# Solenoise.net
KiCad netlist of a schematic drawn in EAGLE
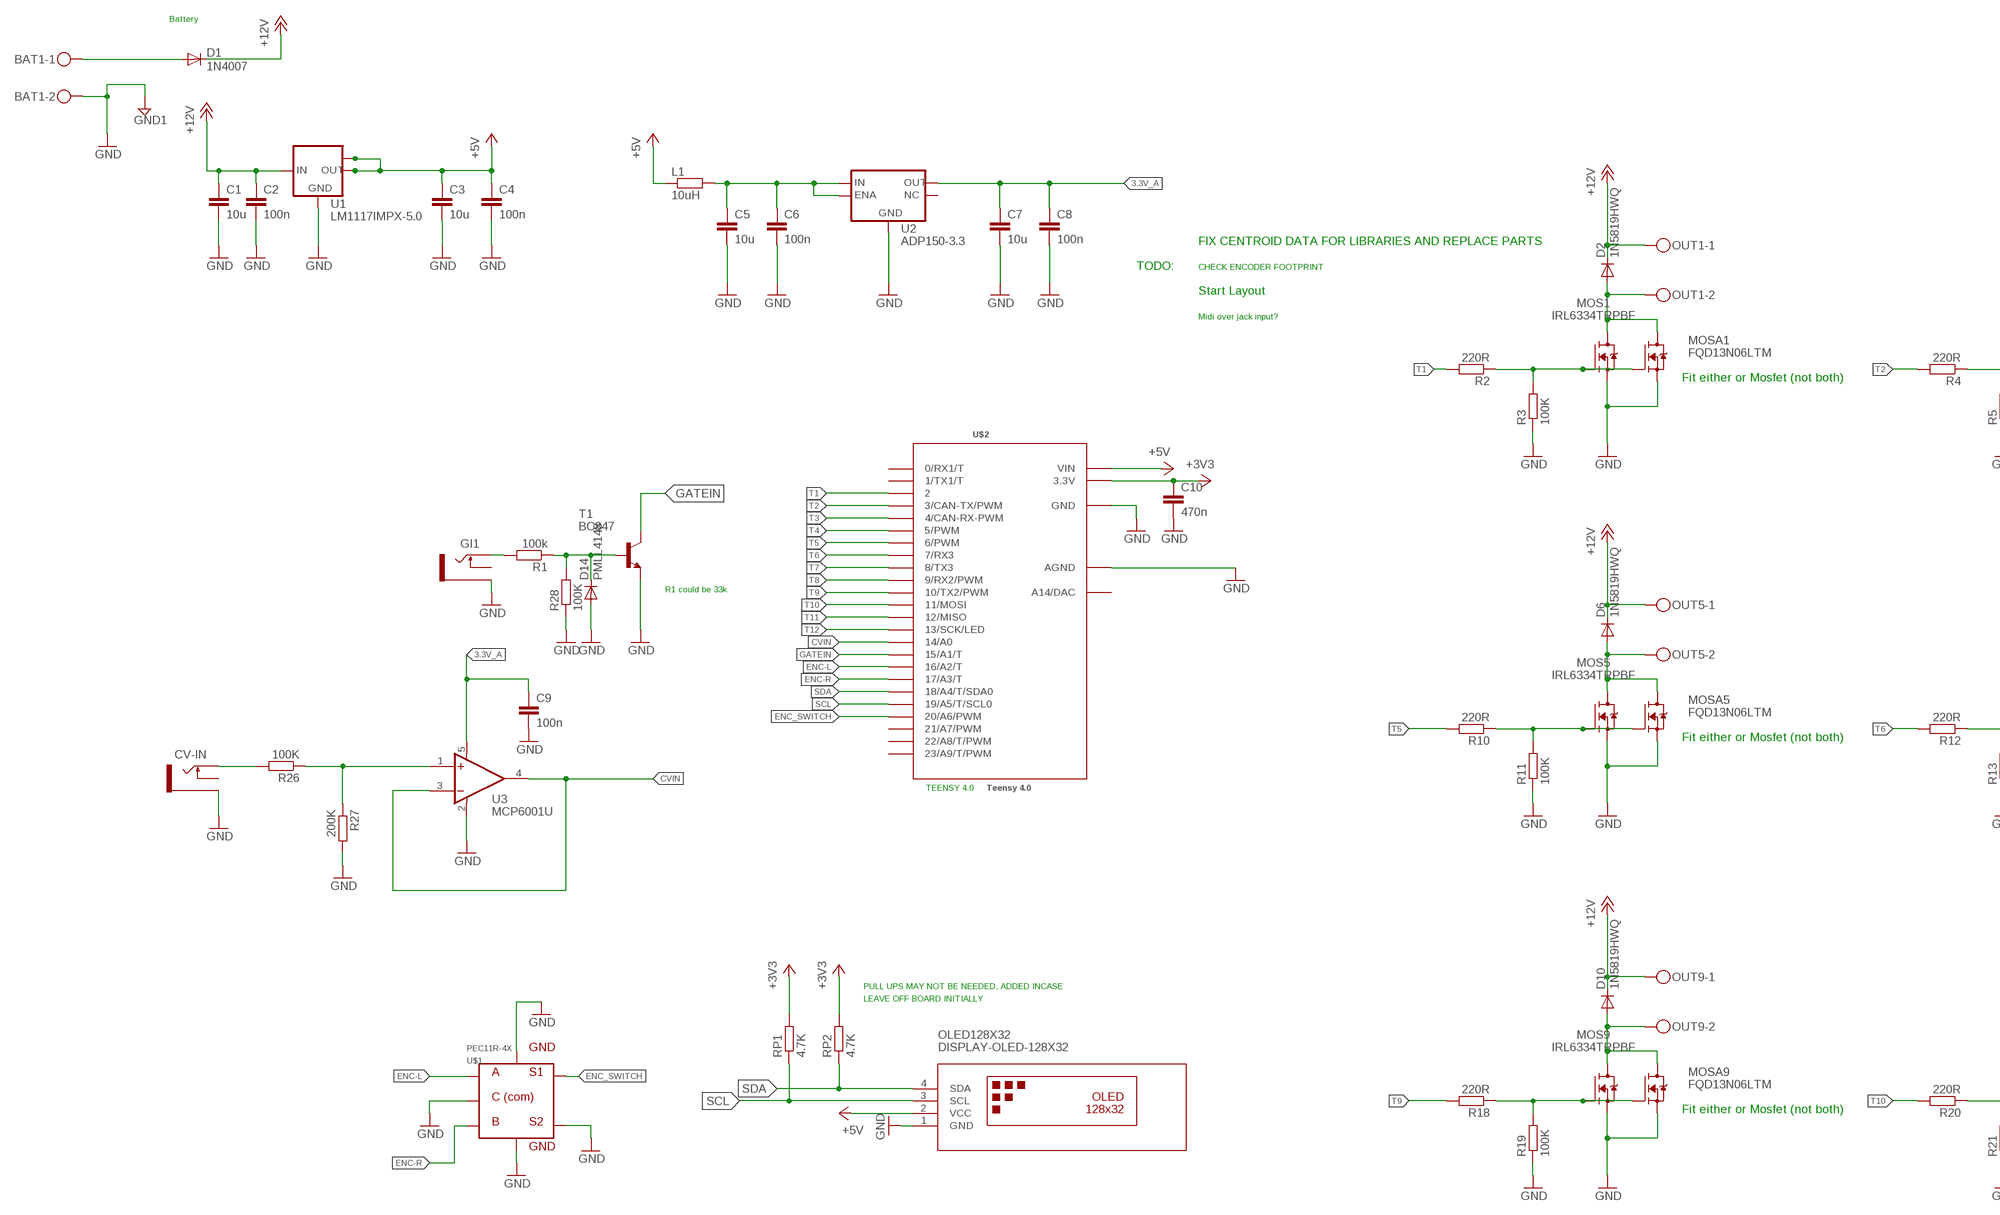
[diagram p0: schematic, sheet 1, part 1 of 2]
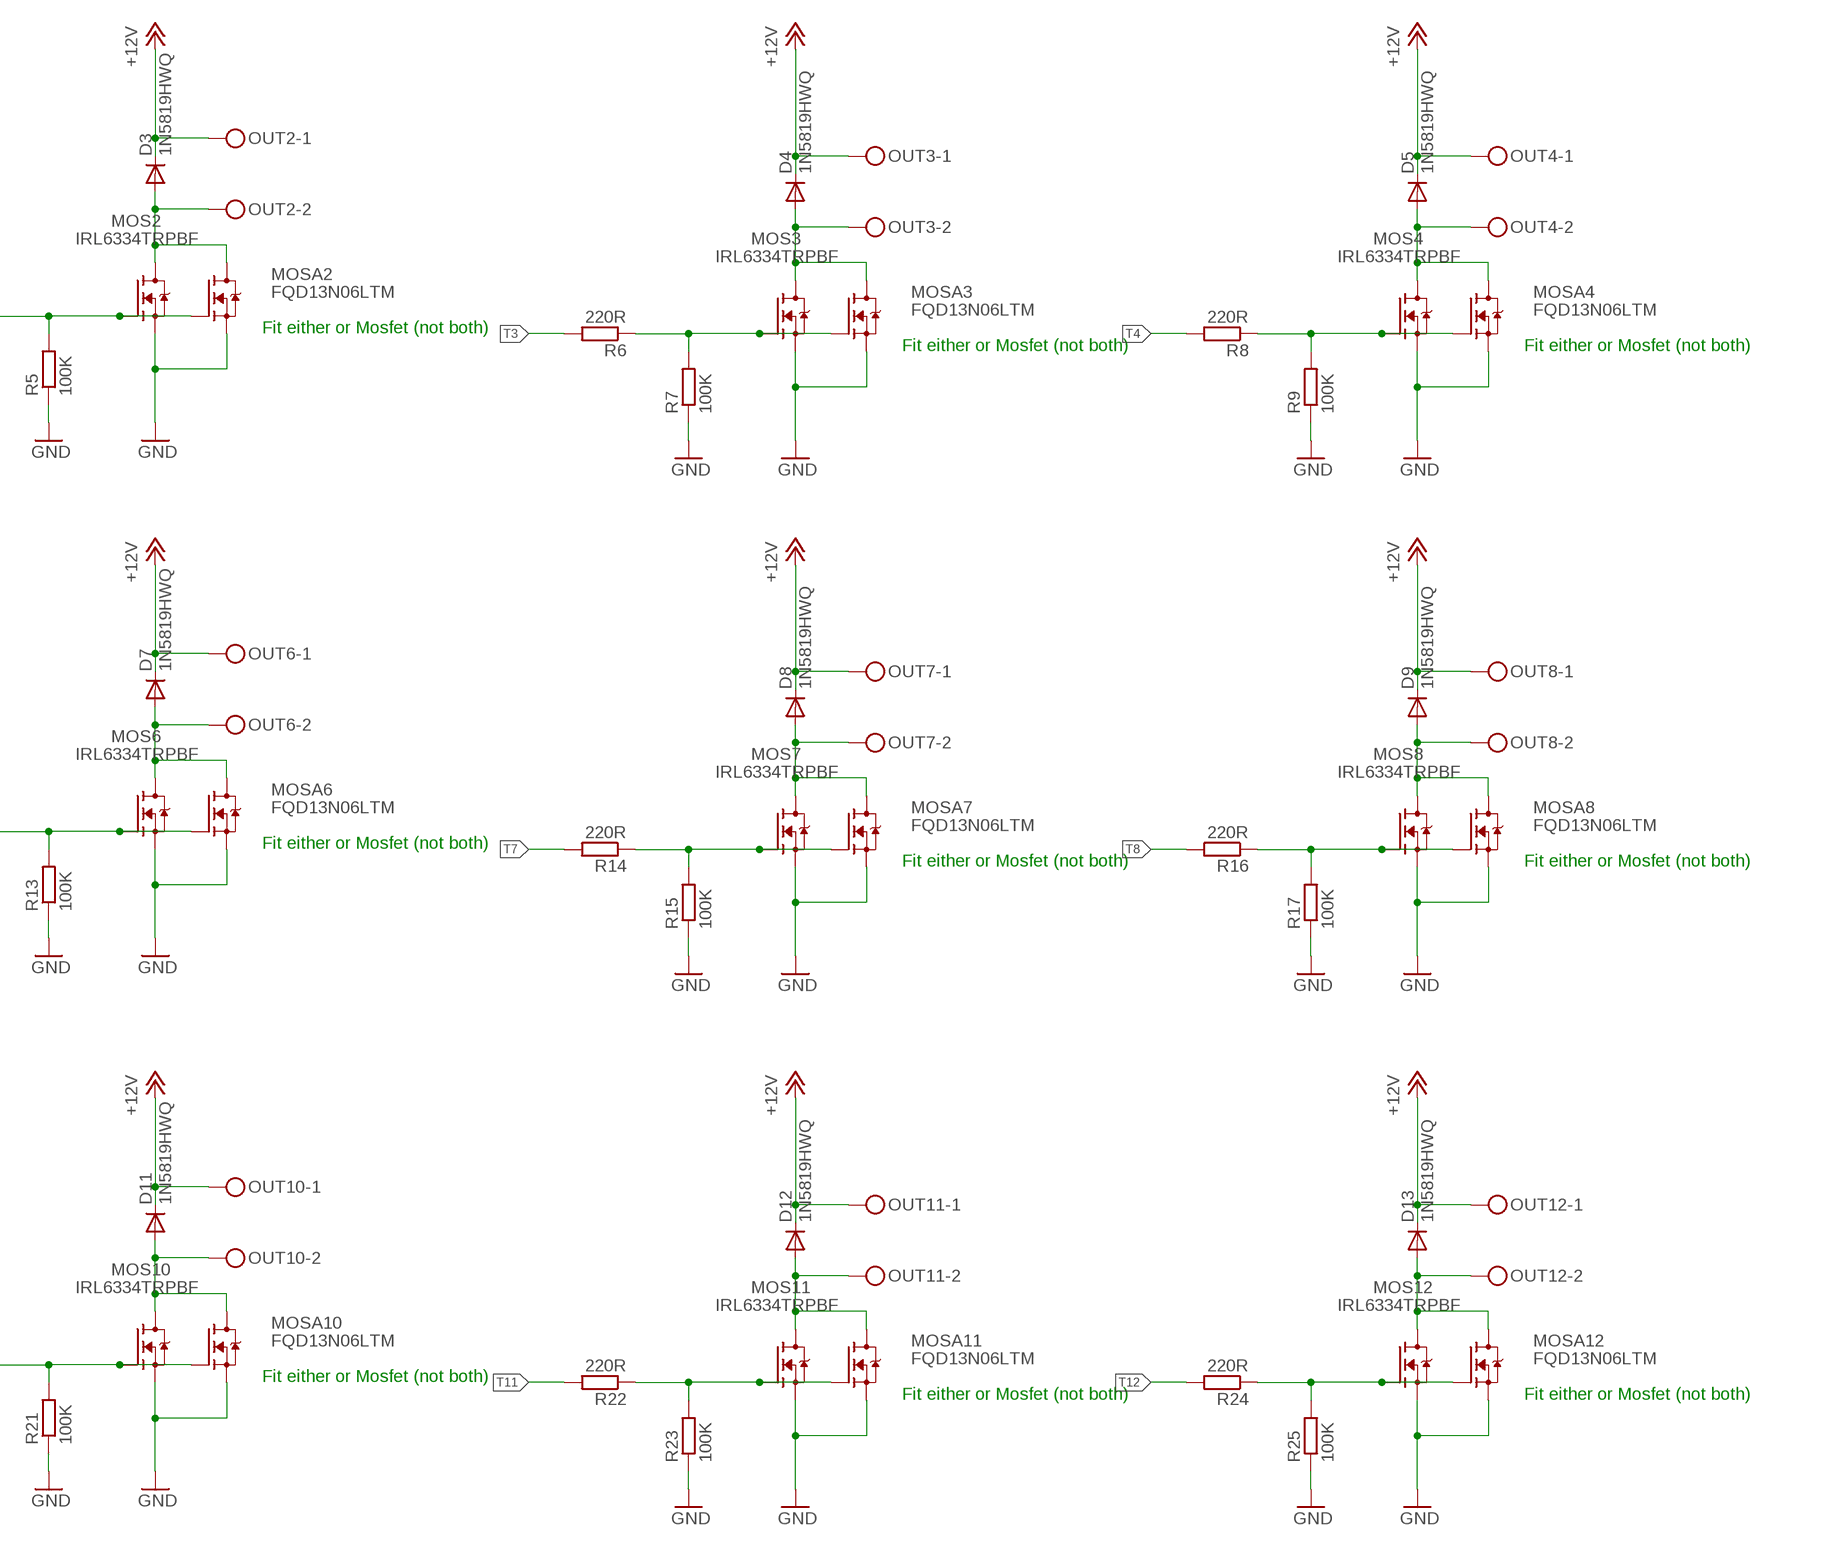
[diagram p1: schematic, sheet 1, part 2 of 2]

(export (version "E")
  (design (tool "Eeschema 10.0.6"))
  (components
    (comp (ref "BAT1")
      (value "MKDSN1,5/2-5,08")
      (footprint "eagle-import:MKDSN1,5_2-5,08")
      (fields (field (name "MPN") "MKDSN 1,5/2-5.08"))
      (libsource (lib "eagle-import") (part "MKDSN1,5/2-5,08"))
    )
    (comp (ref "C1")
      (value "10u")
      (footprint "eagle-import:C1206")
      (libsource (lib "eagle-import") (part "C-EUC1206"))
    )
    (comp (ref "C2")
      (value "100n")
      (footprint "eagle-import:C0805")
      (libsource (lib "eagle-import") (part "C-EUC0805"))
    )
    (comp (ref "C3")
      (value "10u")
      (footprint "eagle-import:C1206")
      (libsource (lib "eagle-import") (part "C-EUC1206"))
    )
    (comp (ref "C4")
      (value "100n")
      (footprint "eagle-import:C0805")
      (libsource (lib "eagle-import") (part "C-EUC0805"))
    )
    (comp (ref "C5")
      (value "10u")
      (footprint "eagle-import:C1206")
      (libsource (lib "eagle-import") (part "C-EUC1206"))
    )
    (comp (ref "C6")
      (value "100n")
      (footprint "eagle-import:C0805")
      (libsource (lib "eagle-import") (part "C-EUC0805"))
    )
    (comp (ref "C7")
      (value "10u")
      (footprint "eagle-import:C1206")
      (libsource (lib "eagle-import") (part "C-EUC1206"))
    )
    (comp (ref "C8")
      (value "100n")
      (footprint "eagle-import:C0805")
      (libsource (lib "eagle-import") (part "C-EUC0805"))
    )
    (comp (ref "C9")
      (value "100n")
      (footprint "eagle-import:C0805")
      (libsource (lib "eagle-import") (part "C-EUC0805"))
    )
    (comp (ref "C10")
      (value "470n")
      (footprint "eagle-import:C0805")
      (libsource (lib "eagle-import") (part "C-EUC0805"))
    )
    (comp (ref "CV-IN")
      (value "THONKICONNNEW")
      (footprint "eagle-import:WQP-PJ301M-12_JACK")
      (libsource (lib "eagle-import") (part "THONKICONNNEW"))
    )
    (comp (ref "D1")
      (value "1N4007")
      (footprint "eagle-import:DO41-10")
      (libsource (lib "eagle-import") (part "1N4004"))
    )
    (comp (ref "D2")
      (value "1N5819HWQ")
      (footprint "eagle-import:SOD123")
      (libsource (lib "eagle-import") (part "MBR0520LT"))
    )
    (comp (ref "D3")
      (value "1N5819HWQ")
      (footprint "eagle-import:SOD123")
      (libsource (lib "eagle-import") (part "MBR0520LT"))
    )
    (comp (ref "D4")
      (value "1N5819HWQ")
      (footprint "eagle-import:SOD123")
      (libsource (lib "eagle-import") (part "MBR0520LT"))
    )
    (comp (ref "D5")
      (value "1N5819HWQ")
      (footprint "eagle-import:SOD123")
      (libsource (lib "eagle-import") (part "MBR0520LT"))
    )
    (comp (ref "D6")
      (value "1N5819HWQ")
      (footprint "eagle-import:SOD123")
      (libsource (lib "eagle-import") (part "MBR0520LT"))
    )
    (comp (ref "D7")
      (value "1N5819HWQ")
      (footprint "eagle-import:SOD123")
      (libsource (lib "eagle-import") (part "MBR0520LT"))
    )
    (comp (ref "D8")
      (value "1N5819HWQ")
      (footprint "eagle-import:SOD123")
      (libsource (lib "eagle-import") (part "MBR0520LT"))
    )
    (comp (ref "D9")
      (value "1N5819HWQ")
      (footprint "eagle-import:SOD123")
      (libsource (lib "eagle-import") (part "MBR0520LT"))
    )
    (comp (ref "D10")
      (value "1N5819HWQ")
      (footprint "eagle-import:SOD123")
      (libsource (lib "eagle-import") (part "MBR0520LT"))
    )
    (comp (ref "D11")
      (value "1N5819HWQ")
      (footprint "eagle-import:SOD123")
      (libsource (lib "eagle-import") (part "MBR0520LT"))
    )
    (comp (ref "D12")
      (value "1N5819HWQ")
      (footprint "eagle-import:SOD123")
      (libsource (lib "eagle-import") (part "MBR0520LT"))
    )
    (comp (ref "D13")
      (value "1N5819HWQ")
      (footprint "eagle-import:SOD123")
      (libsource (lib "eagle-import") (part "MBR0520LT"))
    )
    (comp (ref "D14")
      (value "PMLL4148")
      (footprint "eagle-import:SOD80C")
      (libsource (lib "eagle-import") (part "PMLL4150"))
    )
    (comp (ref "GI1")
      (value "THONKICONNNEW")
      (footprint "eagle-import:WQP-PJ301M-12_JACK")
      (libsource (lib "eagle-import") (part "THONKICONNNEW"))
    )
    (comp (ref "L1")
      (value "10uH")
      (footprint "eagle-import:R0805")
      (libsource (lib "eagle-import") (part "R-EU_R0805"))
    )
    (comp (ref "MOS1")
      (value "IRL6334TRPBF")
      (footprint "eagle-import:IRL6344TRPBF")
      (libsource (lib "eagle-import") (part "IRL6334TRPBF"))
    )
    (comp (ref "MOS2")
      (value "IRL6334TRPBF")
      (footprint "eagle-import:IRL6344TRPBF")
      (libsource (lib "eagle-import") (part "IRL6334TRPBF"))
    )
    (comp (ref "MOS3")
      (value "IRL6334TRPBF")
      (footprint "eagle-import:IRL6344TRPBF")
      (libsource (lib "eagle-import") (part "IRL6334TRPBF"))
    )
    (comp (ref "MOS4")
      (value "IRL6334TRPBF")
      (footprint "eagle-import:IRL6344TRPBF")
      (libsource (lib "eagle-import") (part "IRL6334TRPBF"))
    )
    (comp (ref "MOS5")
      (value "IRL6334TRPBF")
      (footprint "eagle-import:IRL6344TRPBF")
      (libsource (lib "eagle-import") (part "IRL6334TRPBF"))
    )
    (comp (ref "MOS6")
      (value "IRL6334TRPBF")
      (footprint "eagle-import:IRL6344TRPBF")
      (libsource (lib "eagle-import") (part "IRL6334TRPBF"))
    )
    (comp (ref "MOS7")
      (value "IRL6334TRPBF")
      (footprint "eagle-import:IRL6344TRPBF")
      (libsource (lib "eagle-import") (part "IRL6334TRPBF"))
    )
    (comp (ref "MOS8")
      (value "IRL6334TRPBF")
      (footprint "eagle-import:IRL6344TRPBF")
      (libsource (lib "eagle-import") (part "IRL6334TRPBF"))
    )
    (comp (ref "MOS9")
      (value "IRL6334TRPBF")
      (footprint "eagle-import:IRL6344TRPBF")
      (libsource (lib "eagle-import") (part "IRL6334TRPBF"))
    )
    (comp (ref "MOS10")
      (value "IRL6334TRPBF")
      (footprint "eagle-import:IRL6344TRPBF")
      (libsource (lib "eagle-import") (part "IRL6334TRPBF"))
    )
    (comp (ref "MOS11")
      (value "IRL6334TRPBF")
      (footprint "eagle-import:IRL6344TRPBF")
      (libsource (lib "eagle-import") (part "IRL6334TRPBF"))
    )
    (comp (ref "MOS12")
      (value "IRL6334TRPBF")
      (footprint "eagle-import:IRL6344TRPBF")
      (libsource (lib "eagle-import") (part "IRL6334TRPBF"))
    )
    (comp (ref "MOSA1")
      (value "FQD13N06LTM")
      (footprint "eagle-import:FQD13N06LTM")
      (libsource (lib "eagle-import") (part "FQD13N06LTM"))
    )
    (comp (ref "MOSA2")
      (value "FQD13N06LTM")
      (footprint "eagle-import:FQD13N06LTM")
      (libsource (lib "eagle-import") (part "FQD13N06LTM"))
    )
    (comp (ref "MOSA3")
      (value "FQD13N06LTM")
      (footprint "eagle-import:FQD13N06LTM")
      (libsource (lib "eagle-import") (part "FQD13N06LTM"))
    )
    (comp (ref "MOSA4")
      (value "FQD13N06LTM")
      (footprint "eagle-import:FQD13N06LTM")
      (libsource (lib "eagle-import") (part "FQD13N06LTM"))
    )
    (comp (ref "MOSA5")
      (value "FQD13N06LTM")
      (footprint "eagle-import:FQD13N06LTM")
      (libsource (lib "eagle-import") (part "FQD13N06LTM"))
    )
    (comp (ref "MOSA6")
      (value "FQD13N06LTM")
      (footprint "eagle-import:FQD13N06LTM")
      (libsource (lib "eagle-import") (part "FQD13N06LTM"))
    )
    (comp (ref "MOSA7")
      (value "FQD13N06LTM")
      (footprint "eagle-import:FQD13N06LTM")
      (libsource (lib "eagle-import") (part "FQD13N06LTM"))
    )
    (comp (ref "MOSA8")
      (value "FQD13N06LTM")
      (footprint "eagle-import:FQD13N06LTM")
      (libsource (lib "eagle-import") (part "FQD13N06LTM"))
    )
    (comp (ref "MOSA9")
      (value "FQD13N06LTM")
      (footprint "eagle-import:FQD13N06LTM")
      (libsource (lib "eagle-import") (part "FQD13N06LTM"))
    )
    (comp (ref "MOSA10")
      (value "FQD13N06LTM")
      (footprint "eagle-import:FQD13N06LTM")
      (libsource (lib "eagle-import") (part "FQD13N06LTM"))
    )
    (comp (ref "MOSA11")
      (value "FQD13N06LTM")
      (footprint "eagle-import:FQD13N06LTM")
      (libsource (lib "eagle-import") (part "FQD13N06LTM"))
    )
    (comp (ref "MOSA12")
      (value "FQD13N06LTM")
      (footprint "eagle-import:FQD13N06LTM")
      (libsource (lib "eagle-import") (part "FQD13N06LTM"))
    )
    (comp (ref "OLED128X32")
      (value "DISPLAY-OLED-128X32")
      (footprint "eagle-import:DISPLAY-OLED-128X32")
      (libsource (lib "eagle-import") (part "DISPLAY-OLED-128X32"))
    )
    (comp (ref "OUT1")
      (value "MKDSN1,5/2-5,08")
      (footprint "eagle-import:MKDSN1,5_2-5,08")
      (fields (field (name "MPN") "MKDSN 1,5/2-5.08"))
      (libsource (lib "eagle-import") (part "MKDSN1,5/2-5,08"))
    )
    (comp (ref "OUT2")
      (value "MKDSN1,5/2-5,08")
      (footprint "eagle-import:MKDSN1,5_2-5,08")
      (fields (field (name "MPN") "MKDSN 1,5/2-5.08"))
      (libsource (lib "eagle-import") (part "MKDSN1,5/2-5,08"))
    )
    (comp (ref "OUT3")
      (value "MKDSN1,5/2-5,08")
      (footprint "eagle-import:MKDSN1,5_2-5,08")
      (fields (field (name "MPN") "MKDSN 1,5/2-5.08"))
      (libsource (lib "eagle-import") (part "MKDSN1,5/2-5,08"))
    )
    (comp (ref "OUT4")
      (value "MKDSN1,5/2-5,08")
      (footprint "eagle-import:MKDSN1,5_2-5,08")
      (fields (field (name "MPN") "MKDSN 1,5/2-5.08"))
      (libsource (lib "eagle-import") (part "MKDSN1,5/2-5,08"))
    )
    (comp (ref "OUT5")
      (value "MKDSN1,5/2-5,08")
      (footprint "eagle-import:MKDSN1,5_2-5,08")
      (fields (field (name "MPN") "MKDSN 1,5/2-5.08"))
      (libsource (lib "eagle-import") (part "MKDSN1,5/2-5,08"))
    )
    (comp (ref "OUT6")
      (value "MKDSN1,5/2-5,08")
      (footprint "eagle-import:MKDSN1,5_2-5,08")
      (fields (field (name "MPN") "MKDSN 1,5/2-5.08"))
      (libsource (lib "eagle-import") (part "MKDSN1,5/2-5,08"))
    )
    (comp (ref "OUT7")
      (value "MKDSN1,5/2-5,08")
      (footprint "eagle-import:MKDSN1,5_2-5,08")
      (fields (field (name "MPN") "MKDSN 1,5/2-5.08"))
      (libsource (lib "eagle-import") (part "MKDSN1,5/2-5,08"))
    )
    (comp (ref "OUT8")
      (value "MKDSN1,5/2-5,08")
      (footprint "eagle-import:MKDSN1,5_2-5,08")
      (fields (field (name "MPN") "MKDSN 1,5/2-5.08"))
      (libsource (lib "eagle-import") (part "MKDSN1,5/2-5,08"))
    )
    (comp (ref "OUT9")
      (value "MKDSN1,5/2-5,08")
      (footprint "eagle-import:MKDSN1,5_2-5,08")
      (fields (field (name "MPN") "MKDSN 1,5/2-5.08"))
      (libsource (lib "eagle-import") (part "MKDSN1,5/2-5,08"))
    )
    (comp (ref "OUT10")
      (value "MKDSN1,5/2-5,08")
      (footprint "eagle-import:MKDSN1,5_2-5,08")
      (fields (field (name "MPN") "MKDSN 1,5/2-5.08"))
      (libsource (lib "eagle-import") (part "MKDSN1,5/2-5,08"))
    )
    (comp (ref "OUT11")
      (value "MKDSN1,5/2-5,08")
      (footprint "eagle-import:MKDSN1,5_2-5,08")
      (fields (field (name "MPN") "MKDSN 1,5/2-5.08"))
      (libsource (lib "eagle-import") (part "MKDSN1,5/2-5,08"))
    )
    (comp (ref "OUT12")
      (value "MKDSN1,5/2-5,08")
      (footprint "eagle-import:MKDSN1,5_2-5,08")
      (fields (field (name "MPN") "MKDSN 1,5/2-5.08"))
      (libsource (lib "eagle-import") (part "MKDSN1,5/2-5,08"))
    )
    (comp (ref "R1")
      (value "100k")
      (footprint "eagle-import:R0805")
      (libsource (lib "eagle-import") (part "R-EU_R0805"))
    )
    (comp (ref "R2")
      (value "220R")
      (footprint "eagle-import:R0805")
      (libsource (lib "eagle-import") (part "R-EU_R0805"))
    )
    (comp (ref "R3")
      (value "100K")
      (footprint "eagle-import:R0805")
      (libsource (lib "eagle-import") (part "R-EU_R0805"))
    )
    (comp (ref "R4")
      (value "220R")
      (footprint "eagle-import:R0805")
      (libsource (lib "eagle-import") (part "R-EU_R0805"))
    )
    (comp (ref "R5")
      (value "100K")
      (footprint "eagle-import:R0805")
      (libsource (lib "eagle-import") (part "R-EU_R0805"))
    )
    (comp (ref "R6")
      (value "220R")
      (footprint "eagle-import:R0805")
      (libsource (lib "eagle-import") (part "R-EU_R0805"))
    )
    (comp (ref "R7")
      (value "100K")
      (footprint "eagle-import:R0805")
      (libsource (lib "eagle-import") (part "R-EU_R0805"))
    )
    (comp (ref "R8")
      (value "220R")
      (footprint "eagle-import:R0805")
      (libsource (lib "eagle-import") (part "R-EU_R0805"))
    )
    (comp (ref "R9")
      (value "100K")
      (footprint "eagle-import:R0805")
      (libsource (lib "eagle-import") (part "R-EU_R0805"))
    )
    (comp (ref "R10")
      (value "220R")
      (footprint "eagle-import:R0805")
      (libsource (lib "eagle-import") (part "R-EU_R0805"))
    )
    (comp (ref "R11")
      (value "100K")
      (footprint "eagle-import:R0805")
      (libsource (lib "eagle-import") (part "R-EU_R0805"))
    )
    (comp (ref "R12")
      (value "220R")
      (footprint "eagle-import:R0805")
      (libsource (lib "eagle-import") (part "R-EU_R0805"))
    )
    (comp (ref "R13")
      (value "100K")
      (footprint "eagle-import:R0805")
      (libsource (lib "eagle-import") (part "R-EU_R0805"))
    )
    (comp (ref "R14")
      (value "220R")
      (footprint "eagle-import:R0805")
      (libsource (lib "eagle-import") (part "R-EU_R0805"))
    )
    (comp (ref "R15")
      (value "100K")
      (footprint "eagle-import:R0805")
      (libsource (lib "eagle-import") (part "R-EU_R0805"))
    )
    (comp (ref "R16")
      (value "220R")
      (footprint "eagle-import:R0805")
      (libsource (lib "eagle-import") (part "R-EU_R0805"))
    )
    (comp (ref "R17")
      (value "100K")
      (footprint "eagle-import:R0805")
      (libsource (lib "eagle-import") (part "R-EU_R0805"))
    )
    (comp (ref "R18")
      (value "220R")
      (footprint "eagle-import:R0805")
      (libsource (lib "eagle-import") (part "R-EU_R0805"))
    )
    (comp (ref "R19")
      (value "100K")
      (footprint "eagle-import:R0805")
      (libsource (lib "eagle-import") (part "R-EU_R0805"))
    )
    (comp (ref "R20")
      (value "220R")
      (footprint "eagle-import:R0805")
      (libsource (lib "eagle-import") (part "R-EU_R0805"))
    )
    (comp (ref "R21")
      (value "100K")
      (footprint "eagle-import:R0805")
      (libsource (lib "eagle-import") (part "R-EU_R0805"))
    )
    (comp (ref "R22")
      (value "220R")
      (footprint "eagle-import:R0805")
      (libsource (lib "eagle-import") (part "R-EU_R0805"))
    )
    (comp (ref "R23")
      (value "100K")
      (footprint "eagle-import:R0805")
      (libsource (lib "eagle-import") (part "R-EU_R0805"))
    )
    (comp (ref "R24")
      (value "220R")
      (footprint "eagle-import:R0805")
      (libsource (lib "eagle-import") (part "R-EU_R0805"))
    )
    (comp (ref "R25")
      (value "100K")
      (footprint "eagle-import:R0805")
      (libsource (lib "eagle-import") (part "R-EU_R0805"))
    )
    (comp (ref "R26")
      (value "100K")
      (footprint "eagle-import:R0805")
      (libsource (lib "eagle-import") (part "R-EU_R0805"))
    )
    (comp (ref "R27")
      (value "200K")
      (footprint "eagle-import:R0805")
      (libsource (lib "eagle-import") (part "R-EU_R0805"))
    )
    (comp (ref "R28")
      (value "100K")
      (footprint "eagle-import:R0805")
      (libsource (lib "eagle-import") (part "R-EU_R0805"))
    )
    (comp (ref "RP1")
      (value "4.7K")
      (footprint "eagle-import:R0805")
      (libsource (lib "eagle-import") (part "R-EU_R0805"))
    )
    (comp (ref "RP2")
      (value "4.7K")
      (footprint "eagle-import:R0805")
      (libsource (lib "eagle-import") (part "R-EU_R0805"))
    )
    (comp (ref "T1")
      (value "BC847")
      (footprint "eagle-import:SOT23")
      (libsource (lib "eagle-import") (part "BC847"))
    )
    (comp (ref "U$1")
      (value "PEC11R-4X")
      (footprint "eagle-import:ENC")
      (libsource (lib "eagle-import") (part "PEC11R-4X"))
    )
    (comp (ref "U$2")
      (value "Teensy 4.0")
      (footprint "eagle-import:TEENSY_3.1_DAC")
      (libsource (lib "eagle-import") (part "TEENSY_3.1_DAC"))
    )
    (comp (ref "U1")
      (value "LM1117IMPX-5.0")
      (footprint "eagle-import:SOT223")
      (libsource (lib "eagle-import") (part "LM1117IMPX-5.0"))
    )
    (comp (ref "U2")
      (value "ADP150-3.3")
      (footprint "eagle-import:SOT23-5")
      (libsource (lib "eagle-import") (part "ADP150-3.3"))
    )
    (comp (ref "U3")
      (value "MCP6001U")
      (footprint "eagle-import:MCP6001")
      (libsource (lib "eagle-import") (part "MCP6001U"))
    )
  )
  (nets
    (net (code "1") (name "+3V3") (class "Default")
      (node (ref "C10") (pin "1") (pinfunction "1_1") (pintype "passive"))
      (node (ref "RP1") (pin "2") (pinfunction "2_2") (pintype "passive"))
      (node (ref "RP2") (pin "2") (pinfunction "2_2") (pintype "passive"))
      (node (ref "U$2") (pin "3.3V") (pinfunction "3.3V_3.3V") (pintype "power_in"))
    )
    (net (code "2") (name "+5V") (class "Default")
      (node (ref "C3") (pin "1") (pinfunction "1_1") (pintype "passive"))
      (node (ref "C4") (pin "1") (pinfunction "1_1") (pintype "passive"))
      (node (ref "L1") (pin "1") (pinfunction "1_1") (pintype "passive"))
      (node (ref "OLED128X32") (pin "2") (pinfunction "VCC_2") (pintype "power_in"))
      (node (ref "U$2") (pin "VIN") (pinfunction "VIN_VIN") (pintype "power_in"))
      (node (ref "U1") (pin "2") (pinfunction "OUT_2") (pintype "passive"))
      (node (ref "U1") (pin "TAB") (pinfunction "OUT1_TAB") (pintype "passive"))
    )
    (net (code "3") (name "+12V") (class "Default")
      (node (ref "C1") (pin "1") (pinfunction "1_1") (pintype "passive"))
      (node (ref "C2") (pin "1") (pinfunction "1_1") (pintype "passive"))
      (node (ref "D1") (pin "C") (pinfunction "C_C") (pintype "passive"))
      (node (ref "D10") (pin "C") (pinfunction "C_C") (pintype "passive"))
      (node (ref "D11") (pin "C") (pinfunction "C_C") (pintype "passive"))
      (node (ref "D12") (pin "C") (pinfunction "C_C") (pintype "passive"))
      (node (ref "D13") (pin "C") (pinfunction "C_C") (pintype "passive"))
      (node (ref "D2") (pin "C") (pinfunction "C_C") (pintype "passive"))
      (node (ref "D3") (pin "C") (pinfunction "C_C") (pintype "passive"))
      (node (ref "D4") (pin "C") (pinfunction "C_C") (pintype "passive"))
      (node (ref "D5") (pin "C") (pinfunction "C_C") (pintype "passive"))
      (node (ref "D6") (pin "C") (pinfunction "C_C") (pintype "passive"))
      (node (ref "D7") (pin "C") (pinfunction "C_C") (pintype "passive"))
      (node (ref "D8") (pin "C") (pinfunction "C_C") (pintype "passive"))
      (node (ref "D9") (pin "C") (pinfunction "C_C") (pintype "passive"))
      (node (ref "OUT1") (pin "1") (pinfunction "KL_1") (pintype "passive"))
      (node (ref "OUT10") (pin "1") (pinfunction "KL_1") (pintype "passive"))
      (node (ref "OUT11") (pin "1") (pinfunction "KL_1") (pintype "passive"))
      (node (ref "OUT12") (pin "1") (pinfunction "KL_1") (pintype "passive"))
      (node (ref "OUT2") (pin "1") (pinfunction "KL_1") (pintype "passive"))
      (node (ref "OUT3") (pin "1") (pinfunction "KL_1") (pintype "passive"))
      (node (ref "OUT4") (pin "1") (pinfunction "KL_1") (pintype "passive"))
      (node (ref "OUT5") (pin "1") (pinfunction "KL_1") (pintype "passive"))
      (node (ref "OUT6") (pin "1") (pinfunction "KL_1") (pintype "passive"))
      (node (ref "OUT7") (pin "1") (pinfunction "KL_1") (pintype "passive"))
      (node (ref "OUT8") (pin "1") (pinfunction "KL_1") (pintype "passive"))
      (node (ref "OUT9") (pin "1") (pinfunction "KL_1") (pintype "passive"))
      (node (ref "U1") (pin "3") (pinfunction "IN_3") (pintype "input"))
    )
    (net (code "4") (name "3.3V_A") (class "Default")
      (node (ref "C7") (pin "1") (pinfunction "1_1") (pintype "passive"))
      (node (ref "C8") (pin "1") (pinfunction "1_1") (pintype "passive"))
      (node (ref "C9") (pin "1") (pinfunction "1_1") (pintype "passive"))
      (node (ref "U2") (pin "OUT") (pinfunction "VOUT_OUT") (pintype "passive"))
      (node (ref "U3") (pin "5") (pinfunction "V+_5") (pintype "power_in"))
    )
    (net (code "5") (name "CVIN") (class "Default")
      (node (ref "U$2") (pin "14/A0") (pinfunction "14/A0_14/A0") (pintype "bidirectional"))
      (node (ref "U3") (pin "3") (pinfunction "-IN_3") (pintype "input"))
      (node (ref "U3") (pin "4") (pinfunction "OUT_4") (pintype "output"))
    )
    (net (code "6") (name "ENC-L") (class "Default")
      (node (ref "U$1") (pin "A") (pinfunction "A_A") (pintype "passive"))
      (node (ref "U$2") (pin "16/A2") (pinfunction "16/A2/T_16/A2") (pintype "bidirectional"))
    )
    (net (code "7") (name "ENC-R") (class "Default")
      (node (ref "U$1") (pin "B") (pinfunction "B_B") (pintype "passive"))
      (node (ref "U$2") (pin "17/A3") (pinfunction "17/A3/T_17/A3") (pintype "bidirectional"))
    )
    (net (code "8") (name "ENC_SWITCH") (class "Default")
      (node (ref "U$1") (pin "1") (pinfunction "SW1_1") (pintype "passive"))
      (node (ref "U$2") (pin "20/A6") (pinfunction "20/A6/PWM_20/A6") (pintype "bidirectional"))
    )
    (net (code "9") (name "GATEIN") (class "Default")
      (node (ref "T1") (pin "3") (pinfunction "C_3") (pintype "passive"))
      (node (ref "U$2") (pin "15/A1") (pinfunction "15/A1/T_15/A1") (pintype "bidirectional"))
    )
    (net (code "10") (name "GND") (class "Default")
      (node (ref "BAT1") (pin "2") (pinfunction "KL_2") (pintype "passive"))
      (node (ref "C1") (pin "2") (pinfunction "2_2") (pintype "passive"))
      (node (ref "C10") (pin "2") (pinfunction "2_2") (pintype "passive"))
      (node (ref "C2") (pin "2") (pinfunction "2_2") (pintype "passive"))
      (node (ref "C3") (pin "2") (pinfunction "2_2") (pintype "passive"))
      (node (ref "C4") (pin "2") (pinfunction "2_2") (pintype "passive"))
      (node (ref "C5") (pin "2") (pinfunction "2_2") (pintype "passive"))
      (node (ref "C6") (pin "2") (pinfunction "2_2") (pintype "passive"))
      (node (ref "C7") (pin "2") (pinfunction "2_2") (pintype "passive"))
      (node (ref "C8") (pin "2") (pinfunction "2_2") (pintype "passive"))
      (node (ref "C9") (pin "2") (pinfunction "2_2") (pintype "passive"))
      (node (ref "CV-IN") (pin "P$3_SLEEVE") (pinfunction "SLEEVE_P$3_SLEEVE") (pintype "passive"))
      (node (ref "D14") (pin "A") (pinfunction "A_A") (pintype "passive"))
      (node (ref "GI1") (pin "P$3_SLEEVE") (pinfunction "SLEEVE_P$3_SLEEVE") (pintype "passive"))
      (node (ref "MOS1") (pin "2") (pinfunction "S_2") (pintype "passive"))
      (node (ref "MOS10") (pin "2") (pinfunction "S_2") (pintype "passive"))
      (node (ref "MOS11") (pin "2") (pinfunction "S_2") (pintype "passive"))
      (node (ref "MOS12") (pin "2") (pinfunction "S_2") (pintype "passive"))
      (node (ref "MOS2") (pin "2") (pinfunction "S_2") (pintype "passive"))
      (node (ref "MOS3") (pin "2") (pinfunction "S_2") (pintype "passive"))
      (node (ref "MOS4") (pin "2") (pinfunction "S_2") (pintype "passive"))
      (node (ref "MOS5") (pin "2") (pinfunction "S_2") (pintype "passive"))
      (node (ref "MOS6") (pin "2") (pinfunction "S_2") (pintype "passive"))
      (node (ref "MOS7") (pin "2") (pinfunction "S_2") (pintype "passive"))
      (node (ref "MOS8") (pin "2") (pinfunction "S_2") (pintype "passive"))
      (node (ref "MOS9") (pin "2") (pinfunction "S_2") (pintype "passive"))
      (node (ref "MOSA1") (pin "2") (pinfunction "S_2") (pintype "passive"))
      (node (ref "MOSA10") (pin "2") (pinfunction "S_2") (pintype "passive"))
      (node (ref "MOSA11") (pin "2") (pinfunction "S_2") (pintype "passive"))
      (node (ref "MOSA12") (pin "2") (pinfunction "S_2") (pintype "passive"))
      (node (ref "MOSA2") (pin "2") (pinfunction "S_2") (pintype "passive"))
      (node (ref "MOSA3") (pin "2") (pinfunction "S_2") (pintype "passive"))
      (node (ref "MOSA4") (pin "2") (pinfunction "S_2") (pintype "passive"))
      (node (ref "MOSA5") (pin "2") (pinfunction "S_2") (pintype "passive"))
      (node (ref "MOSA6") (pin "2") (pinfunction "S_2") (pintype "passive"))
      (node (ref "MOSA7") (pin "2") (pinfunction "S_2") (pintype "passive"))
      (node (ref "MOSA8") (pin "2") (pinfunction "S_2") (pintype "passive"))
      (node (ref "MOSA9") (pin "2") (pinfunction "S_2") (pintype "passive"))
      (node (ref "OLED128X32") (pin "1") (pinfunction "GND_1") (pintype "power_in"))
      (node (ref "R11") (pin "1") (pinfunction "1_1") (pintype "passive"))
      (node (ref "R13") (pin "1") (pinfunction "1_1") (pintype "passive"))
      (node (ref "R15") (pin "1") (pinfunction "1_1") (pintype "passive"))
      (node (ref "R17") (pin "1") (pinfunction "1_1") (pintype "passive"))
      (node (ref "R19") (pin "1") (pinfunction "1_1") (pintype "passive"))
      (node (ref "R21") (pin "1") (pinfunction "1_1") (pintype "passive"))
      (node (ref "R23") (pin "1") (pinfunction "1_1") (pintype "passive"))
      (node (ref "R25") (pin "1") (pinfunction "1_1") (pintype "passive"))
      (node (ref "R27") (pin "2") (pinfunction "2_2") (pintype "passive"))
      (node (ref "R28") (pin "1") (pinfunction "1_1") (pintype "passive"))
      (node (ref "R3") (pin "1") (pinfunction "1_1") (pintype "passive"))
      (node (ref "R5") (pin "1") (pinfunction "1_1") (pintype "passive"))
      (node (ref "R7") (pin "1") (pinfunction "1_1") (pintype "passive"))
      (node (ref "R9") (pin "1") (pinfunction "1_1") (pintype "passive"))
      (node (ref "T1") (pin "2") (pinfunction "E_2") (pintype "passive"))
      (node (ref "U$1") (pin "2") (pinfunction "SW2_2") (pintype "passive"))
      (node (ref "U$1") (pin "C") (pinfunction "C_C") (pintype "passive"))
      (node (ref "U$1") (pin "GND1") (pinfunction "GND1_GND1") (pintype "passive"))
      (node (ref "U$1") (pin "GND2") (pinfunction "GND2_GND2") (pintype "passive"))
      (node (ref "U$2") (pin "AGND") (pinfunction "AGND_AGND") (pintype "power_in"))
      (node (ref "U$2") (pin "GND") (pinfunction "GND_GND") (pintype "power_in"))
      (node (ref "U1") (pin "1") (pinfunction "GND_1") (pintype "input"))
      (node (ref "U2") (pin "GND") (pinfunction "GND_GND") (pintype "input"))
      (node (ref "U3") (pin "2") (pinfunction "V-_2") (pintype "power_in"))
    )
    (net (code "11") (name "Net-(BAT1A-KL)") (class "Default")
      (node (ref "BAT1") (pin "1") (pinfunction "KL_1") (pintype "passive"))
      (node (ref "D1") (pin "A") (pinfunction "A_A") (pintype "passive"))
    )
    (net (code "12") (name "Net-(CV-IN-TIP)") (class "Default")
      (node (ref "CV-IN") (pin "P$1_TIP") (pinfunction "TIP_P$1_TIP") (pintype "passive"))
      (node (ref "R26") (pin "2") (pinfunction "2_2") (pintype "passive"))
    )
    (net (code "13") (name "Net-(GI1-TIP)") (class "Default")
      (node (ref "GI1") (pin "P$1_TIP") (pinfunction "TIP_P$1_TIP") (pintype "passive"))
      (node (ref "R1") (pin "2") (pinfunction "2_2") (pintype "passive"))
    )
    (net (code "14") (name "Net-(MOS1-D)") (class "Default")
      (node (ref "D2") (pin "A") (pinfunction "A_A") (pintype "passive"))
      (node (ref "MOS1") (pin "3") (pinfunction "D_3") (pintype "passive"))
      (node (ref "MOSA1") (pin "3") (pinfunction "D_3") (pintype "passive"))
      (node (ref "OUT1") (pin "2") (pinfunction "KL_2") (pintype "passive"))
    )
    (net (code "15") (name "Net-(MOS1-G)") (class "Default")
      (node (ref "MOS1") (pin "1") (pinfunction "G_1") (pintype "passive"))
      (node (ref "MOSA1") (pin "1") (pinfunction "G_1") (pintype "passive"))
      (node (ref "R2") (pin "1") (pinfunction "1_1") (pintype "passive"))
      (node (ref "R3") (pin "2") (pinfunction "2_2") (pintype "passive"))
    )
    (net (code "16") (name "Net-(MOS2-D)") (class "Default")
      (node (ref "D3") (pin "A") (pinfunction "A_A") (pintype "passive"))
      (node (ref "MOS2") (pin "3") (pinfunction "D_3") (pintype "passive"))
      (node (ref "MOSA2") (pin "3") (pinfunction "D_3") (pintype "passive"))
      (node (ref "OUT2") (pin "2") (pinfunction "KL_2") (pintype "passive"))
    )
    (net (code "17") (name "Net-(MOS2-G)") (class "Default")
      (node (ref "MOS2") (pin "1") (pinfunction "G_1") (pintype "passive"))
      (node (ref "MOSA2") (pin "1") (pinfunction "G_1") (pintype "passive"))
      (node (ref "R4") (pin "1") (pinfunction "1_1") (pintype "passive"))
      (node (ref "R5") (pin "2") (pinfunction "2_2") (pintype "passive"))
    )
    (net (code "18") (name "Net-(MOS3-D)") (class "Default")
      (node (ref "D4") (pin "A") (pinfunction "A_A") (pintype "passive"))
      (node (ref "MOS3") (pin "3") (pinfunction "D_3") (pintype "passive"))
      (node (ref "MOSA3") (pin "3") (pinfunction "D_3") (pintype "passive"))
      (node (ref "OUT3") (pin "2") (pinfunction "KL_2") (pintype "passive"))
    )
    (net (code "19") (name "Net-(MOS3-G)") (class "Default")
      (node (ref "MOS3") (pin "1") (pinfunction "G_1") (pintype "passive"))
      (node (ref "MOSA3") (pin "1") (pinfunction "G_1") (pintype "passive"))
      (node (ref "R6") (pin "1") (pinfunction "1_1") (pintype "passive"))
      (node (ref "R7") (pin "2") (pinfunction "2_2") (pintype "passive"))
    )
    (net (code "20") (name "Net-(MOS4-D)") (class "Default")
      (node (ref "D5") (pin "A") (pinfunction "A_A") (pintype "passive"))
      (node (ref "MOS4") (pin "3") (pinfunction "D_3") (pintype "passive"))
      (node (ref "MOSA4") (pin "3") (pinfunction "D_3") (pintype "passive"))
      (node (ref "OUT4") (pin "2") (pinfunction "KL_2") (pintype "passive"))
    )
    (net (code "21") (name "Net-(MOS4-G)") (class "Default")
      (node (ref "MOS4") (pin "1") (pinfunction "G_1") (pintype "passive"))
      (node (ref "MOSA4") (pin "1") (pinfunction "G_1") (pintype "passive"))
      (node (ref "R8") (pin "1") (pinfunction "1_1") (pintype "passive"))
      (node (ref "R9") (pin "2") (pinfunction "2_2") (pintype "passive"))
    )
    (net (code "22") (name "Net-(MOS5-D)") (class "Default")
      (node (ref "D6") (pin "A") (pinfunction "A_A") (pintype "passive"))
      (node (ref "MOS5") (pin "3") (pinfunction "D_3") (pintype "passive"))
      (node (ref "MOSA5") (pin "3") (pinfunction "D_3") (pintype "passive"))
      (node (ref "OUT5") (pin "2") (pinfunction "KL_2") (pintype "passive"))
    )
    (net (code "23") (name "Net-(MOS5-G)") (class "Default")
      (node (ref "MOS5") (pin "1") (pinfunction "G_1") (pintype "passive"))
      (node (ref "MOSA5") (pin "1") (pinfunction "G_1") (pintype "passive"))
      (node (ref "R10") (pin "1") (pinfunction "1_1") (pintype "passive"))
      (node (ref "R11") (pin "2") (pinfunction "2_2") (pintype "passive"))
    )
    (net (code "24") (name "Net-(MOS6-D)") (class "Default")
      (node (ref "D7") (pin "A") (pinfunction "A_A") (pintype "passive"))
      (node (ref "MOS6") (pin "3") (pinfunction "D_3") (pintype "passive"))
      (node (ref "MOSA6") (pin "3") (pinfunction "D_3") (pintype "passive"))
      (node (ref "OUT6") (pin "2") (pinfunction "KL_2") (pintype "passive"))
    )
    (net (code "25") (name "Net-(MOS6-G)") (class "Default")
      (node (ref "MOS6") (pin "1") (pinfunction "G_1") (pintype "passive"))
      (node (ref "MOSA6") (pin "1") (pinfunction "G_1") (pintype "passive"))
      (node (ref "R12") (pin "1") (pinfunction "1_1") (pintype "passive"))
      (node (ref "R13") (pin "2") (pinfunction "2_2") (pintype "passive"))
    )
    (net (code "26") (name "Net-(MOS7-D)") (class "Default")
      (node (ref "D8") (pin "A") (pinfunction "A_A") (pintype "passive"))
      (node (ref "MOS7") (pin "3") (pinfunction "D_3") (pintype "passive"))
      (node (ref "MOSA7") (pin "3") (pinfunction "D_3") (pintype "passive"))
      (node (ref "OUT7") (pin "2") (pinfunction "KL_2") (pintype "passive"))
    )
    (net (code "27") (name "Net-(MOS7-G)") (class "Default")
      (node (ref "MOS7") (pin "1") (pinfunction "G_1") (pintype "passive"))
      (node (ref "MOSA7") (pin "1") (pinfunction "G_1") (pintype "passive"))
      (node (ref "R14") (pin "1") (pinfunction "1_1") (pintype "passive"))
      (node (ref "R15") (pin "2") (pinfunction "2_2") (pintype "passive"))
    )
    (net (code "28") (name "Net-(MOS8-D)") (class "Default")
      (node (ref "D9") (pin "A") (pinfunction "A_A") (pintype "passive"))
      (node (ref "MOS8") (pin "3") (pinfunction "D_3") (pintype "passive"))
      (node (ref "MOSA8") (pin "3") (pinfunction "D_3") (pintype "passive"))
      (node (ref "OUT8") (pin "2") (pinfunction "KL_2") (pintype "passive"))
    )
    (net (code "29") (name "Net-(MOS8-G)") (class "Default")
      (node (ref "MOS8") (pin "1") (pinfunction "G_1") (pintype "passive"))
      (node (ref "MOSA8") (pin "1") (pinfunction "G_1") (pintype "passive"))
      (node (ref "R16") (pin "1") (pinfunction "1_1") (pintype "passive"))
      (node (ref "R17") (pin "2") (pinfunction "2_2") (pintype "passive"))
    )
    (net (code "30") (name "Net-(MOS9-D)") (class "Default")
      (node (ref "D10") (pin "A") (pinfunction "A_A") (pintype "passive"))
      (node (ref "MOS9") (pin "3") (pinfunction "D_3") (pintype "passive"))
      (node (ref "MOSA9") (pin "3") (pinfunction "D_3") (pintype "passive"))
      (node (ref "OUT9") (pin "2") (pinfunction "KL_2") (pintype "passive"))
    )
    (net (code "31") (name "Net-(MOS9-G)") (class "Default")
      (node (ref "MOS9") (pin "1") (pinfunction "G_1") (pintype "passive"))
      (node (ref "MOSA9") (pin "1") (pinfunction "G_1") (pintype "passive"))
      (node (ref "R18") (pin "1") (pinfunction "1_1") (pintype "passive"))
      (node (ref "R19") (pin "2") (pinfunction "2_2") (pintype "passive"))
    )
    (net (code "32") (name "Net-(MOS10-D)") (class "Default")
      (node (ref "D11") (pin "A") (pinfunction "A_A") (pintype "passive"))
      (node (ref "MOS10") (pin "3") (pinfunction "D_3") (pintype "passive"))
      (node (ref "MOSA10") (pin "3") (pinfunction "D_3") (pintype "passive"))
      (node (ref "OUT10") (pin "2") (pinfunction "KL_2") (pintype "passive"))
    )
    (net (code "33") (name "Net-(MOS10-G)") (class "Default")
      (node (ref "MOS10") (pin "1") (pinfunction "G_1") (pintype "passive"))
      (node (ref "MOSA10") (pin "1") (pinfunction "G_1") (pintype "passive"))
      (node (ref "R20") (pin "1") (pinfunction "1_1") (pintype "passive"))
      (node (ref "R21") (pin "2") (pinfunction "2_2") (pintype "passive"))
    )
    (net (code "34") (name "Net-(MOS11-D)") (class "Default")
      (node (ref "D12") (pin "A") (pinfunction "A_A") (pintype "passive"))
      (node (ref "MOS11") (pin "3") (pinfunction "D_3") (pintype "passive"))
      (node (ref "MOSA11") (pin "3") (pinfunction "D_3") (pintype "passive"))
      (node (ref "OUT11") (pin "2") (pinfunction "KL_2") (pintype "passive"))
    )
    (net (code "35") (name "Net-(MOS11-G)") (class "Default")
      (node (ref "MOS11") (pin "1") (pinfunction "G_1") (pintype "passive"))
      (node (ref "MOSA11") (pin "1") (pinfunction "G_1") (pintype "passive"))
      (node (ref "R22") (pin "1") (pinfunction "1_1") (pintype "passive"))
      (node (ref "R23") (pin "2") (pinfunction "2_2") (pintype "passive"))
    )
    (net (code "36") (name "Net-(MOS12-D)") (class "Default")
      (node (ref "D13") (pin "A") (pinfunction "A_A") (pintype "passive"))
      (node (ref "MOS12") (pin "3") (pinfunction "D_3") (pintype "passive"))
      (node (ref "MOSA12") (pin "3") (pinfunction "D_3") (pintype "passive"))
      (node (ref "OUT12") (pin "2") (pinfunction "KL_2") (pintype "passive"))
    )
    (net (code "37") (name "Net-(MOS12-G)") (class "Default")
      (node (ref "MOS12") (pin "1") (pinfunction "G_1") (pintype "passive"))
      (node (ref "MOSA12") (pin "1") (pinfunction "G_1") (pintype "passive"))
      (node (ref "R24") (pin "1") (pinfunction "1_1") (pintype "passive"))
      (node (ref "R25") (pin "2") (pinfunction "2_2") (pintype "passive"))
    )
    (net (code "38") (name "Net-(T1-B)") (class "Default")
      (node (ref "D14") (pin "C") (pinfunction "C_C") (pintype "passive"))
      (node (ref "R1") (pin "1") (pinfunction "1_1") (pintype "passive"))
      (node (ref "R28") (pin "2") (pinfunction "2_2") (pintype "passive"))
      (node (ref "T1") (pin "1") (pinfunction "B_1") (pintype "passive"))
    )
    (net (code "39") (name "Net-(U2-ENA)") (class "Default")
      (node (ref "C5") (pin "1") (pinfunction "1_1") (pintype "passive"))
      (node (ref "C6") (pin "1") (pinfunction "1_1") (pintype "passive"))
      (node (ref "L1") (pin "2") (pinfunction "2_2") (pintype "passive"))
      (node (ref "U2") (pin "EN") (pinfunction "ENA_EN") (pintype "input"))
      (node (ref "U2") (pin "VIN") (pinfunction "IN_VIN") (pintype "input"))
    )
    (net (code "40") (name "Net-(U3-+IN)") (class "Default")
      (node (ref "R26") (pin "1") (pinfunction "1_1") (pintype "passive"))
      (node (ref "R27") (pin "1") (pinfunction "1_1") (pintype "passive"))
      (node (ref "U3") (pin "1") (pinfunction "+IN_1") (pintype "input"))
    )
    (net (code "41") (name "SCL") (class "Default")
      (node (ref "OLED128X32") (pin "3") (pinfunction "SCL_3") (pintype "bidirectional"))
      (node (ref "RP1") (pin "1") (pinfunction "1_1") (pintype "passive"))
      (node (ref "U$2") (pin "19/A5") (pinfunction "19/A5/T/SCL0_19/A5") (pintype "bidirectional"))
    )
    (net (code "42") (name "SDA") (class "Default")
      (node (ref "OLED128X32") (pin "4") (pinfunction "SDA_4") (pintype "bidirectional"))
      (node (ref "RP2") (pin "1") (pinfunction "1_1") (pintype "passive"))
      (node (ref "U$2") (pin "18/A4") (pinfunction "18/A4/T/SDA0_18/A4") (pintype "bidirectional"))
    )
    (net (code "43") (name "T1") (class "Default")
      (node (ref "R2") (pin "2") (pinfunction "2_2") (pintype "passive"))
      (node (ref "U$2") (pin "2") (pinfunction "2_2") (pintype "bidirectional"))
    )
    (net (code "44") (name "T2") (class "Default")
      (node (ref "R4") (pin "2") (pinfunction "2_2") (pintype "passive"))
      (node (ref "U$2") (pin "3") (pinfunction "3/CAN-TX/PWM_3") (pintype "bidirectional"))
    )
    (net (code "45") (name "T3") (class "Default")
      (node (ref "R6") (pin "2") (pinfunction "2_2") (pintype "passive"))
      (node (ref "U$2") (pin "4") (pinfunction "4/CAN-RX-PWM_4") (pintype "bidirectional"))
    )
    (net (code "46") (name "T4") (class "Default")
      (node (ref "R8") (pin "2") (pinfunction "2_2") (pintype "passive"))
      (node (ref "U$2") (pin "5") (pinfunction "5/PWM_5") (pintype "bidirectional"))
    )
    (net (code "47") (name "T5") (class "Default")
      (node (ref "R10") (pin "2") (pinfunction "2_2") (pintype "passive"))
      (node (ref "U$2") (pin "6") (pinfunction "6/PWM_6") (pintype "bidirectional"))
    )
    (net (code "48") (name "T6") (class "Default")
      (node (ref "R12") (pin "2") (pinfunction "2_2") (pintype "passive"))
      (node (ref "U$2") (pin "7") (pinfunction "7/RX3_7") (pintype "bidirectional"))
    )
    (net (code "49") (name "T7") (class "Default")
      (node (ref "R14") (pin "2") (pinfunction "2_2") (pintype "passive"))
      (node (ref "U$2") (pin "8") (pinfunction "8/TX3_8") (pintype "bidirectional"))
    )
    (net (code "50") (name "T8") (class "Default")
      (node (ref "R16") (pin "2") (pinfunction "2_2") (pintype "passive"))
      (node (ref "U$2") (pin "9") (pinfunction "9/RX2/PWM_9") (pintype "bidirectional"))
    )
    (net (code "51") (name "T9") (class "Default")
      (node (ref "R18") (pin "2") (pinfunction "2_2") (pintype "passive"))
      (node (ref "U$2") (pin "10") (pinfunction "10/TX2/PWM_10") (pintype "bidirectional"))
    )
    (net (code "52") (name "T10") (class "Default")
      (node (ref "R20") (pin "2") (pinfunction "2_2") (pintype "passive"))
      (node (ref "U$2") (pin "11") (pinfunction "11/MOSI_11") (pintype "bidirectional"))
    )
    (net (code "53") (name "T11") (class "Default")
      (node (ref "R22") (pin "2") (pinfunction "2_2") (pintype "passive"))
      (node (ref "U$2") (pin "12") (pinfunction "12/MISO_12") (pintype "bidirectional"))
    )
    (net (code "54") (name "T12") (class "Default")
      (node (ref "R24") (pin "2") (pinfunction "2_2") (pintype "passive"))
      (node (ref "U$2") (pin "13") (pinfunction "13/SCK/LED_13") (pintype "bidirectional"))
    )
    (net (code "55") (name "unconnected-(CV-IN-SWITCH-PadP$2_SWITCH)") (class "Default")
      (node (ref "CV-IN") (pin "P$2_SWITCH") (pinfunction "SWITCH_P$2_SWITCH") (pintype "passive"))
    )
    (net (code "56") (name "unconnected-(GI1-SWITCH-PadP$2_SWITCH)") (class "Default")
      (node (ref "GI1") (pin "P$2_SWITCH") (pinfunction "SWITCH_P$2_SWITCH") (pintype "passive"))
    )
    (net (code "57") (name "unconnected-(U$2-0{slash}RX1{slash}T-Pad0)") (class "Default")
      (node (ref "U$2") (pin "0") (pinfunction "0/RX1/T_0") (pintype "bidirectional"))
    )
    (net (code "58") (name "unconnected-(U$2-1{slash}TX1{slash}T-Pad1)") (class "Default")
      (node (ref "U$2") (pin "1") (pinfunction "1/TX1/T_1") (pintype "bidirectional"))
    )
    (net (code "59") (name "unconnected-(U$2-21{slash}A7{slash}PWM-Pad21{slash}A7)") (class "Default")
      (node (ref "U$2") (pin "21/A7") (pinfunction "21/A7/PWM_21/A7") (pintype "bidirectional"))
    )
    (net (code "60") (name "unconnected-(U$2-22{slash}A8{slash}T{slash}PWM-Pad22{slash}A8)") (class "Default")
      (node (ref "U$2") (pin "22/A8") (pinfunction "22/A8/T/PWM_22/A8") (pintype "bidirectional"))
    )
    (net (code "61") (name "unconnected-(U$2-23{slash}A9{slash}T{slash}PWM-Pad23{slash}A9)") (class "Default")
      (node (ref "U$2") (pin "23/A9") (pinfunction "23/A9/T/PWM_23/A9") (pintype "bidirectional"))
    )
    (net (code "62") (name "unconnected-(U$2-A14{slash}DAC-PadRESET{slash}DAC)") (class "Default")
      (node (ref "U$2") (pin "RESET/DAC") (pinfunction "A14/DAC_RESET/DAC") (pintype "bidirectional"))
    )
    (net (code "63") (name "unconnected-(U2-PadNC)") (class "Default")
      (node (ref "U2") (pin "NC") (pinfunction "NC_NC") (pintype "passive"))
    )
  )
)
